# secon_analog_in.net
KiCad netlist of a schematic drawn in Altium Designer
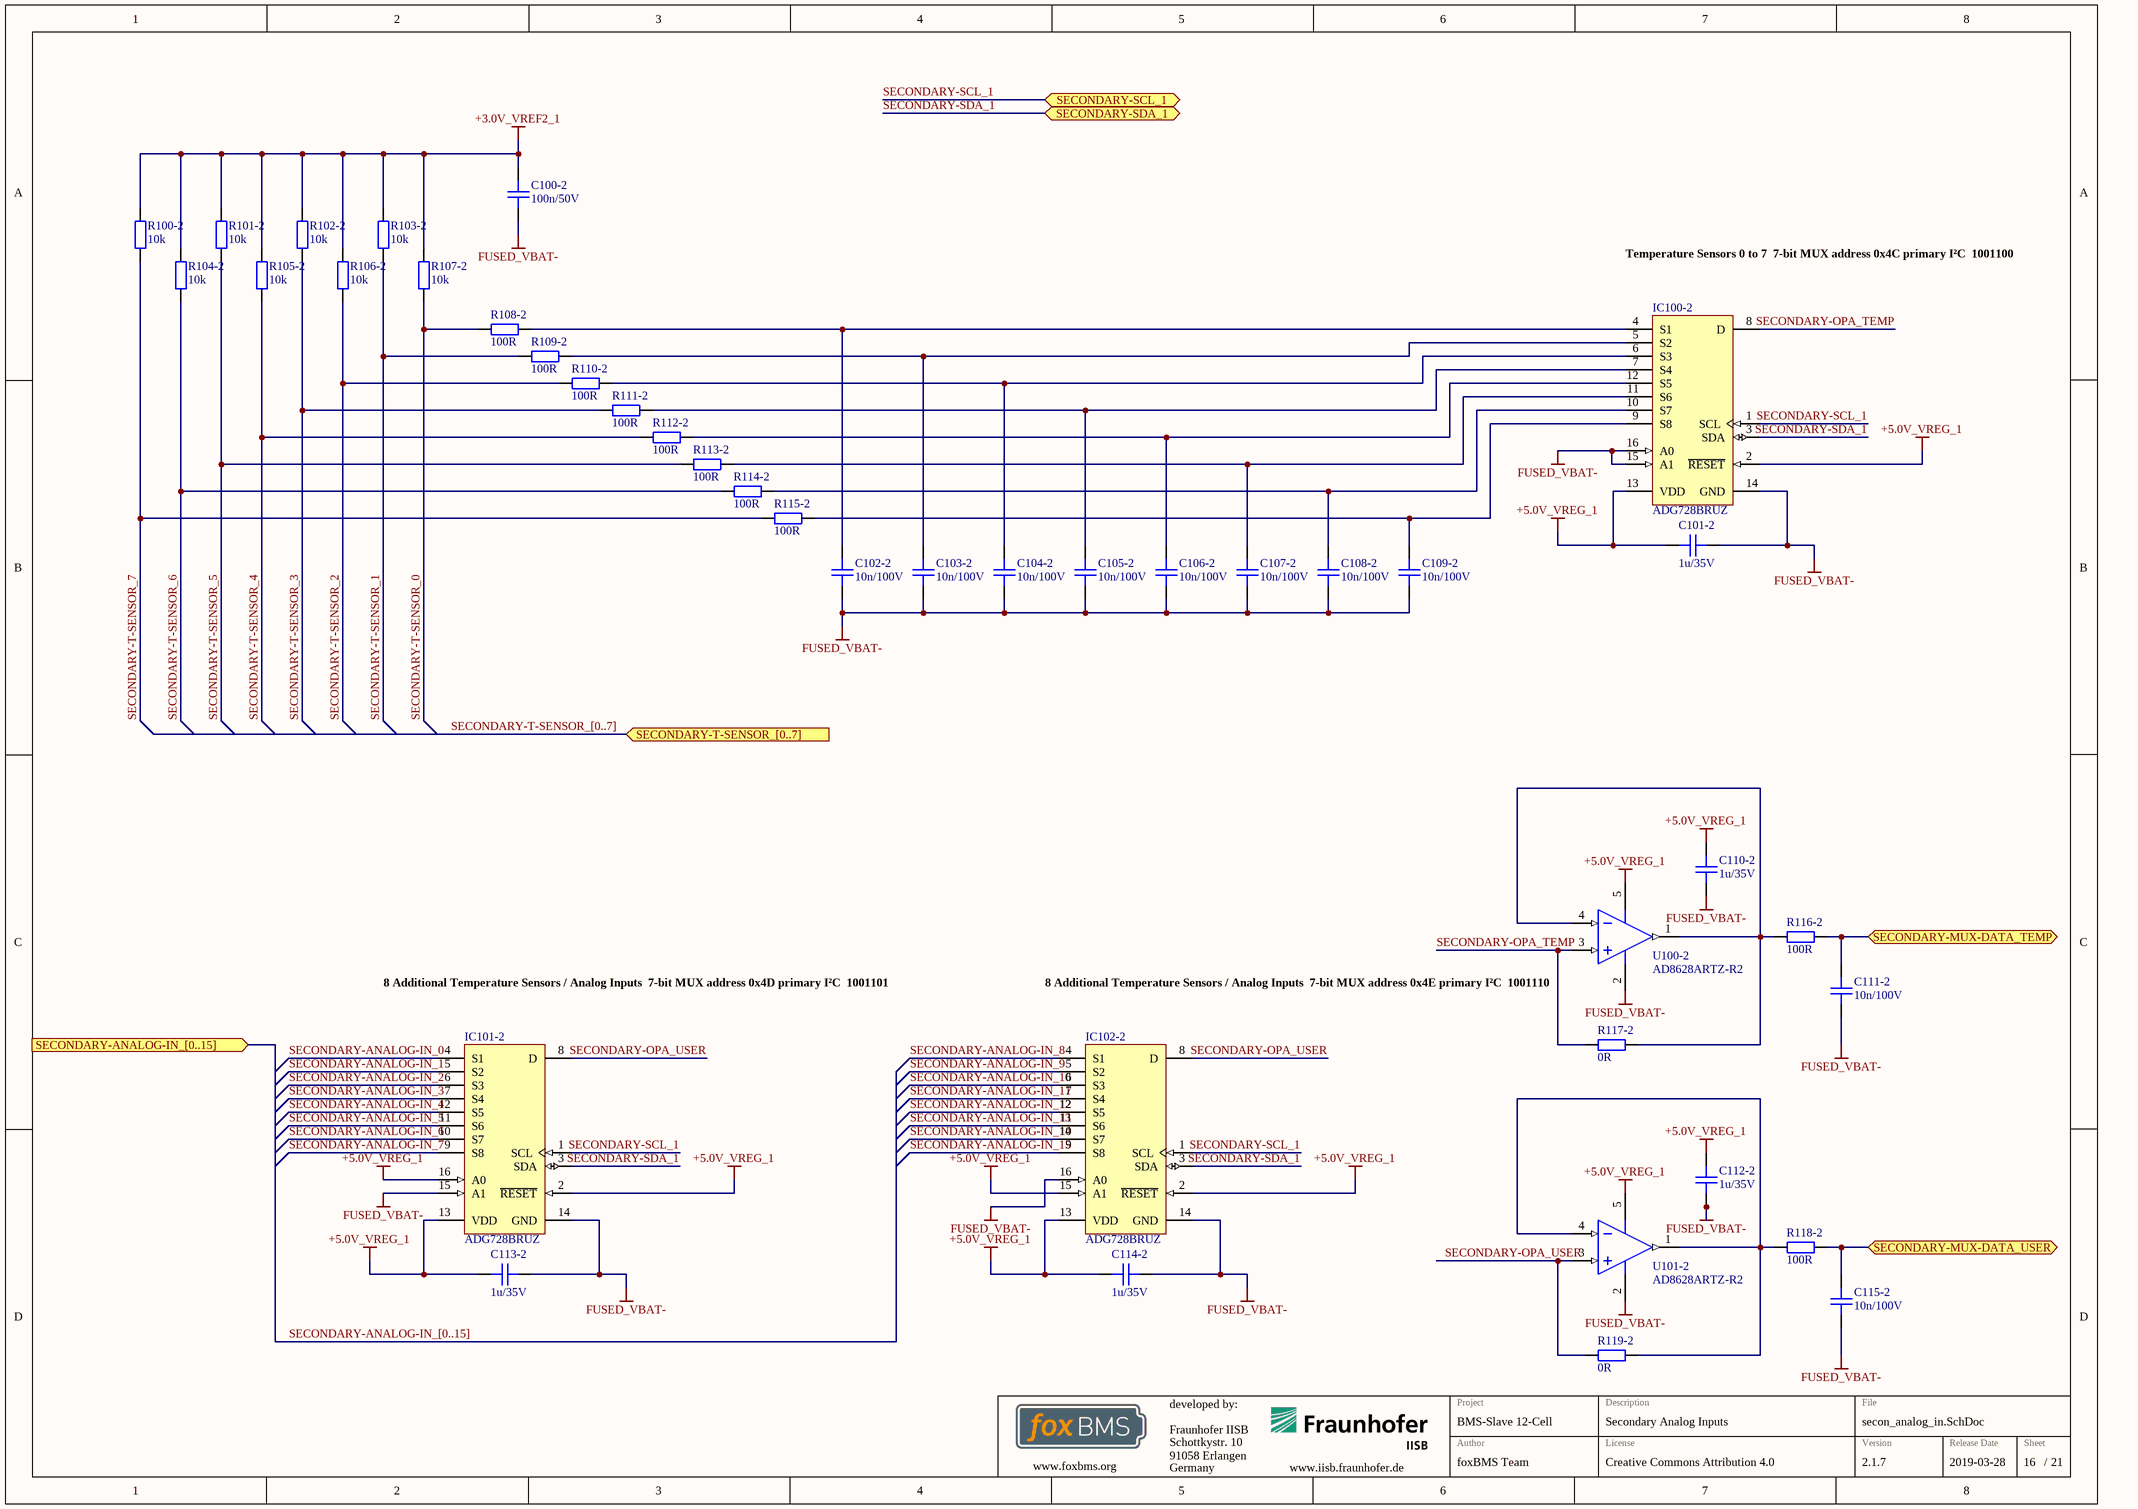
[diagram p0: secon_analog_in.SchDoc]

(export (version "E")
  (design (tool "Eeschema 10.0.6"))
  (components
    (comp (ref "C100-2")
      (value "100n/50V")
      (footprint "CAPC1608X08N")
      (description "MLCC")
      (fields (field (name "PART NUMBER") "gen_C_ceramic_100n_50V_X7R_0603"))
      (libsource (lib "OE750") (part "C"))
    )
    (comp (ref "C101-2")
      (value "1u/35V")
      (footprint "CAPC1608X08N")
      (description "MLCC")
      (fields (field (name "PART NUMBER") "gen_C_ceramic_1u_35V_X7R_0603"))
      (libsource (lib "OE750") (part "C"))
    )
    (comp (ref "C102-2")
      (value "10n/100V")
      (footprint "CAPC1608X08N")
      (description "MLCC")
      (fields (field (name "PART NUMBER") "gen_C_ceramic_10n_100V_X7R_0603"))
      (libsource (lib "OE750") (part "C"))
    )
    (comp (ref "C103-2")
      (value "10n/100V")
      (footprint "CAPC1608X08N")
      (description "MLCC")
      (fields (field (name "PART NUMBER") "gen_C_ceramic_10n_100V_X7R_0603"))
      (libsource (lib "OE750") (part "C"))
    )
    (comp (ref "C104-2")
      (value "10n/100V")
      (footprint "CAPC1608X08N")
      (description "MLCC")
      (fields (field (name "PART NUMBER") "gen_C_ceramic_10n_100V_X7R_0603"))
      (libsource (lib "OE750") (part "C"))
    )
    (comp (ref "C105-2")
      (value "10n/100V")
      (footprint "CAPC1608X08N")
      (description "MLCC")
      (fields (field (name "PART NUMBER") "gen_C_ceramic_10n_100V_X7R_0603"))
      (libsource (lib "OE750") (part "C"))
    )
    (comp (ref "C106-2")
      (value "10n/100V")
      (footprint "CAPC1608X08N")
      (description "MLCC")
      (fields (field (name "PART NUMBER") "gen_C_ceramic_10n_100V_X7R_0603"))
      (libsource (lib "OE750") (part "C"))
    )
    (comp (ref "C107-2")
      (value "10n/100V")
      (footprint "CAPC1608X08N")
      (description "MLCC")
      (fields (field (name "PART NUMBER") "gen_C_ceramic_10n_100V_X7R_0603"))
      (libsource (lib "OE750") (part "C"))
    )
    (comp (ref "C108-2")
      (value "10n/100V")
      (footprint "CAPC1608X08N")
      (description "MLCC")
      (fields (field (name "PART NUMBER") "gen_C_ceramic_10n_100V_X7R_0603"))
      (libsource (lib "OE750") (part "C"))
    )
    (comp (ref "C109-2")
      (value "10n/100V")
      (footprint "CAPC1608X08N")
      (description "MLCC")
      (fields (field (name "PART NUMBER") "gen_C_ceramic_10n_100V_X7R_0603"))
      (libsource (lib "OE750") (part "C"))
    )
    (comp (ref "C110-2")
      (value "1u/35V")
      (footprint "CAPC1608X08N")
      (description "MLCC")
      (fields (field (name "PART NUMBER") "gen_C_ceramic_1u_35V_X7R_0603"))
      (libsource (lib "OE750") (part "C"))
    )
    (comp (ref "C111-2")
      (value "10n/100V")
      (footprint "CAPC1608X08N")
      (description "MLCC")
      (fields (field (name "PART NUMBER") "gen_C_ceramic_10n_100V_X7R_0603"))
      (libsource (lib "OE750") (part "C"))
    )
    (comp (ref "C112-2")
      (value "1u/35V")
      (footprint "CAPC1608X08N")
      (description "MLCC")
      (fields (field (name "PART NUMBER") "gen_C_ceramic_1u_35V_X7R_0603"))
      (libsource (lib "OE750") (part "C"))
    )
    (comp (ref "C113-2")
      (value "1u/35V")
      (footprint "CAPC1608X08N")
      (description "MLCC")
      (fields (field (name "PART NUMBER") "gen_C_ceramic_1u_35V_X7R_0603"))
      (libsource (lib "OE750") (part "C"))
    )
    (comp (ref "C114-2")
      (value "1u/35V")
      (footprint "CAPC1608X08N")
      (description "MLCC")
      (fields (field (name "PART NUMBER") "gen_C_ceramic_1u_35V_X7R_0603"))
      (libsource (lib "OE750") (part "C"))
    )
    (comp (ref "C115-2")
      (value "10n/100V")
      (footprint "CAPC1608X08N")
      (description "MLCC")
      (fields (field (name "PART NUMBER") "gen_C_ceramic_10n_100V_X7R_0603"))
      (libsource (lib "OE750") (part "C"))
    )
    (comp (ref "IC100-2")
      (value "ADG728BRUZ")
      (footprint "ADI-RU-16_M")
      (fields (field (name "MANUFACTURER") "Analog Devices"))
      (libsource (lib "Altium Content Vault") (part "ADI-ADG728-RU-16"))
    )
    (comp (ref "IC101-2")
      (value "ADG728BRUZ")
      (footprint "ADI-RU-16_M")
      (fields (field (name "MANUFACTURER") "Analog Devices"))
      (libsource (lib "Altium Content Vault") (part "ADI-ADG728-RU-16"))
    )
    (comp (ref "IC102-2")
      (value "ADG728BRUZ")
      (footprint "ADI-RU-16_M")
      (fields (field (name "MANUFACTURER") "Analog Devices"))
      (libsource (lib "Altium Content Vault") (part "ADI-ADG728-RU-16"))
    )
    (comp (ref "R100-2")
      (value "10k")
      (footprint "RESC1608X05N")
      (description "SMD Resistor 10k 0603")
      (fields (field (name "PART NUMBER") "gen_R_10k_0603") (field (name "TOLERANCE") "1%"))
      (libsource (lib "OE750") (part "R"))
    )
    (comp (ref "R101-2")
      (value "10k")
      (footprint "RESC1608X05N")
      (description "SMD Resistor 10k 0603")
      (fields (field (name "PART NUMBER") "gen_R_10k_0603") (field (name "TOLERANCE") "1%"))
      (libsource (lib "OE750") (part "R"))
    )
    (comp (ref "R102-2")
      (value "10k")
      (footprint "RESC1608X05N")
      (description "SMD Resistor 10k 0603")
      (fields (field (name "PART NUMBER") "gen_R_10k_0603") (field (name "TOLERANCE") "1%"))
      (libsource (lib "OE750") (part "R"))
    )
    (comp (ref "R103-2")
      (value "10k")
      (footprint "RESC1608X05N")
      (description "SMD Resistor 10k 0603")
      (fields (field (name "PART NUMBER") "gen_R_10k_0603") (field (name "TOLERANCE") "1%"))
      (libsource (lib "OE750") (part "R"))
    )
    (comp (ref "R104-2")
      (value "10k")
      (footprint "RESC1608X05N")
      (description "SMD Resistor 10k 0603")
      (fields (field (name "PART NUMBER") "gen_R_10k_0603") (field (name "TOLERANCE") "1%"))
      (libsource (lib "OE750") (part "R"))
    )
    (comp (ref "R105-2")
      (value "10k")
      (footprint "RESC1608X05N")
      (description "SMD Resistor 10k 0603")
      (fields (field (name "PART NUMBER") "gen_R_10k_0603") (field (name "TOLERANCE") "1%"))
      (libsource (lib "OE750") (part "R"))
    )
    (comp (ref "R106-2")
      (value "10k")
      (footprint "RESC1608X05N")
      (description "SMD Resistor 10k 0603")
      (fields (field (name "PART NUMBER") "gen_R_10k_0603") (field (name "TOLERANCE") "1%"))
      (libsource (lib "OE750") (part "R"))
    )
    (comp (ref "R107-2")
      (value "10k")
      (footprint "RESC1608X05N")
      (description "SMD Resistor 10k 0603")
      (fields (field (name "PART NUMBER") "gen_R_10k_0603") (field (name "TOLERANCE") "1%"))
      (libsource (lib "OE750") (part "R"))
    )
    (comp (ref "R108-2")
      (value "100R")
      (footprint "RESC1608X05N")
      (description "SMD Resistor 100R 0603")
      (fields (field (name "PART NUMBER") "gen_R_100R_0603") (field (name "TOLERANCE") "1%"))
      (libsource (lib "OE750") (part "R"))
    )
    (comp (ref "R109-2")
      (value "100R")
      (footprint "RESC1608X05N")
      (description "SMD Resistor 100R 0603")
      (fields (field (name "PART NUMBER") "gen_R_100R_0603") (field (name "TOLERANCE") "1%"))
      (libsource (lib "OE750") (part "R"))
    )
    (comp (ref "R110-2")
      (value "100R")
      (footprint "RESC1608X05N")
      (description "SMD Resistor 100R 0603")
      (fields (field (name "PART NUMBER") "gen_R_100R_0603") (field (name "TOLERANCE") "1%"))
      (libsource (lib "OE750") (part "R"))
    )
    (comp (ref "R111-2")
      (value "100R")
      (footprint "RESC1608X05N")
      (description "SMD Resistor 100R 0603")
      (fields (field (name "PART NUMBER") "gen_R_100R_0603") (field (name "TOLERANCE") "1%"))
      (libsource (lib "OE750") (part "R"))
    )
    (comp (ref "R112-2")
      (value "100R")
      (footprint "RESC1608X05N")
      (description "SMD Resistor 100R 0603")
      (fields (field (name "PART NUMBER") "gen_R_100R_0603") (field (name "TOLERANCE") "1%"))
      (libsource (lib "OE750") (part "R"))
    )
    (comp (ref "R113-2")
      (value "100R")
      (footprint "RESC1608X05N")
      (description "SMD Resistor 100R 0603")
      (fields (field (name "PART NUMBER") "gen_R_100R_0603") (field (name "TOLERANCE") "1%"))
      (libsource (lib "OE750") (part "R"))
    )
    (comp (ref "R114-2")
      (value "100R")
      (footprint "RESC1608X05N")
      (description "SMD Resistor 100R 0603")
      (fields (field (name "PART NUMBER") "gen_R_100R_0603") (field (name "TOLERANCE") "1%"))
      (libsource (lib "OE750") (part "R"))
    )
    (comp (ref "R115-2")
      (value "100R")
      (footprint "RESC1608X05N")
      (description "SMD Resistor 100R 0603")
      (fields (field (name "PART NUMBER") "gen_R_100R_0603") (field (name "TOLERANCE") "1%"))
      (libsource (lib "OE750") (part "R"))
    )
    (comp (ref "R116-2")
      (value "100R")
      (footprint "RESC1608X05N")
      (description "SMD Resistor 100R 0603")
      (fields (field (name "PART NUMBER") "gen_R_100R_0603") (field (name "TOLERANCE") "1%"))
      (libsource (lib "OE750") (part "R"))
    )
    (comp (ref "R117-2")
      (value "0R")
      (footprint "RESC1608X05N")
      (description "SMD Resistor 0R 0603")
      (fields (field (name "PART NUMBER") "gen_R_0R_0603") (field (name "POWER") "0.1W"))
      (libsource (lib "OE750") (part "R"))
    )
    (comp (ref "R118-2")
      (value "100R")
      (footprint "RESC1608X05N")
      (description "SMD Resistor 100R 0603")
      (fields (field (name "PART NUMBER") "gen_R_100R_0603") (field (name "TOLERANCE") "1%"))
      (libsource (lib "OE750") (part "R"))
    )
    (comp (ref "R119-2")
      (value "0R")
      (footprint "RESC1608X05N")
      (description "SMD Resistor 0R 0603")
      (fields (field (name "PART NUMBER") "gen_R_0R_0603") (field (name "POWER") "0.1W"))
      (libsource (lib "OE750") (part "R"))
    )
    (comp (ref "U100-2")
      (value "AD8628ARTZ-R2")
      (footprint "ADI-RJ-5_M")
      (fields (field (name "MANUFACTURER") "Analog Devices") (field (name "GENERIC PART NUMBER") "AD8628"))
      (libsource (lib "Altium Content Vault") (part "ADI-ADxxxx-X-5"))
    )
    (comp (ref "U101-2")
      (value "AD8628ARTZ-R2")
      (footprint "ADI-RJ-5_M")
      (fields (field (name "MANUFACTURER") "Analog Devices") (field (name "GENERIC PART NUMBER") "AD8628"))
      (libsource (lib "Altium Content Vault") (part "ADI-ADxxxx-X-5"))
    )
  )
  (nets
    (net (code "1") (name "+3.0V_VREF2_1") (class "Default")
      (node (ref "C100-2") (pin "2") (pinfunction "2_2") (pintype "passive"))
      (node (ref "R100-2") (pin "2") (pinfunction "2_2") (pintype "passive"))
      (node (ref "R101-2") (pin "2") (pinfunction "2_2") (pintype "passive"))
      (node (ref "R102-2") (pin "2") (pinfunction "2_2") (pintype "passive"))
      (node (ref "R103-2") (pin "2") (pinfunction "2_2") (pintype "passive"))
      (node (ref "R104-2") (pin "2") (pinfunction "2_2") (pintype "passive"))
      (node (ref "R105-2") (pin "2") (pinfunction "2_2") (pintype "passive"))
      (node (ref "R106-2") (pin "2") (pinfunction "2_2") (pintype "passive"))
      (node (ref "R107-2") (pin "2") (pinfunction "2_2") (pintype "passive"))
    )
    (net (code "2") (name "+5.0V_VREG_1") (class "Default")
      (node (ref "C101-2") (pin "2") (pinfunction "2_2") (pintype "passive"))
      (node (ref "C110-2") (pin "2") (pinfunction "2_2") (pintype "passive"))
      (node (ref "C112-2") (pin "2") (pinfunction "2_2") (pintype "passive"))
      (node (ref "C113-2") (pin "2") (pinfunction "2_2") (pintype "passive"))
      (node (ref "C114-2") (pin "2") (pinfunction "2_2") (pintype "passive"))
      (node (ref "IC100-2") (pin "13") (pinfunction "VDD_13") (pintype "power_in"))
      (node (ref "IC100-2") (pin "2") (pinfunction "~{RESET}_2") (pintype "input"))
      (node (ref "IC101-2") (pin "13") (pinfunction "VDD_13") (pintype "power_in"))
      (node (ref "IC101-2") (pin "16") (pinfunction "A0_16") (pintype "input"))
      (node (ref "IC101-2") (pin "2") (pinfunction "~{RESET}_2") (pintype "input"))
      (node (ref "IC102-2") (pin "13") (pinfunction "VDD_13") (pintype "power_in"))
      (node (ref "IC102-2") (pin "15") (pinfunction "A1_15") (pintype "input"))
      (node (ref "IC102-2") (pin "2") (pinfunction "~{RESET}_2") (pintype "input"))
      (node (ref "U100-2") (pin "5") (pinfunction "+V_5") (pintype "power_in"))
      (node (ref "U101-2") (pin "5") (pinfunction "+V_5") (pintype "power_in"))
    )
    (net (code "3") (name "/SECONDARY-ANALOG-IN_0") (class "Default")
      (node (ref "IC101-2") (pin "4") (pinfunction "S1_4") (pintype "passive"))
    )
    (net (code "4") (name "/SECONDARY-ANALOG-IN_1") (class "Default")
      (node (ref "IC101-2") (pin "5") (pinfunction "S2_5") (pintype "passive"))
    )
    (net (code "5") (name "/SECONDARY-ANALOG-IN_2") (class "Default")
      (node (ref "IC101-2") (pin "6") (pinfunction "S3_6") (pintype "passive"))
    )
    (net (code "6") (name "/SECONDARY-ANALOG-IN_3") (class "Default")
      (node (ref "IC101-2") (pin "7") (pinfunction "S4_7") (pintype "passive"))
    )
    (net (code "7") (name "/SECONDARY-ANALOG-IN_4") (class "Default")
      (node (ref "IC101-2") (pin "12") (pinfunction "S5_12") (pintype "passive"))
    )
    (net (code "8") (name "/SECONDARY-ANALOG-IN_5") (class "Default")
      (node (ref "IC101-2") (pin "11") (pinfunction "S6_11") (pintype "passive"))
    )
    (net (code "9") (name "/SECONDARY-ANALOG-IN_6") (class "Default")
      (node (ref "IC101-2") (pin "10") (pinfunction "S7_10") (pintype "passive"))
    )
    (net (code "10") (name "/SECONDARY-ANALOG-IN_7") (class "Default")
      (node (ref "IC101-2") (pin "9") (pinfunction "S8_9") (pintype "passive"))
    )
    (net (code "11") (name "/SECONDARY-ANALOG-IN_8") (class "Default")
      (node (ref "IC102-2") (pin "4") (pinfunction "S1_4") (pintype "passive"))
    )
    (net (code "12") (name "/SECONDARY-ANALOG-IN_9") (class "Default")
      (node (ref "IC102-2") (pin "5") (pinfunction "S2_5") (pintype "passive"))
    )
    (net (code "13") (name "/SECONDARY-ANALOG-IN_10") (class "Default")
      (node (ref "IC102-2") (pin "6") (pinfunction "S3_6") (pintype "passive"))
    )
    (net (code "14") (name "/SECONDARY-ANALOG-IN_11") (class "Default")
      (node (ref "IC102-2") (pin "7") (pinfunction "S4_7") (pintype "passive"))
    )
    (net (code "15") (name "/SECONDARY-ANALOG-IN_12") (class "Default")
      (node (ref "IC102-2") (pin "12") (pinfunction "S5_12") (pintype "passive"))
    )
    (net (code "16") (name "/SECONDARY-ANALOG-IN_13") (class "Default")
      (node (ref "IC102-2") (pin "11") (pinfunction "S6_11") (pintype "passive"))
    )
    (net (code "17") (name "/SECONDARY-ANALOG-IN_14") (class "Default")
      (node (ref "IC102-2") (pin "10") (pinfunction "S7_10") (pintype "passive"))
    )
    (net (code "18") (name "/SECONDARY-ANALOG-IN_15") (class "Default")
      (node (ref "IC102-2") (pin "9") (pinfunction "S8_9") (pintype "passive"))
    )
    (net (code "20") (name "/SECONDARY-MUX-DATA_TEMP") (class "Default")
      (node (ref "C111-2") (pin "2") (pinfunction "2_2") (pintype "passive"))
      (node (ref "R116-2") (pin "2") (pinfunction "2_2") (pintype "passive"))
    )
    (net (code "21") (name "/SECONDARY-MUX-DATA_USER") (class "Default")
      (node (ref "C115-2") (pin "2") (pinfunction "2_2") (pintype "passive"))
      (node (ref "R118-2") (pin "2") (pinfunction "2_2") (pintype "passive"))
    )
    (net (code "22") (name "/SECONDARY-OPA_TEMP") (class "Default")
      (node (ref "IC100-2") (pin "8") (pinfunction "D_8") (pintype "passive"))
      (node (ref "R117-2") (pin "1") (pinfunction "1_1") (pintype "passive"))
      (node (ref "U100-2") (pin "3") (pinfunction "+IN_3") (pintype "input"))
    )
    (net (code "23") (name "/SECONDARY-OPA_USER") (class "Default")
      (node (ref "IC101-2") (pin "8") (pinfunction "D_8") (pintype "passive"))
      (node (ref "IC102-2") (pin "8") (pinfunction "D_8") (pintype "passive"))
      (node (ref "R119-2") (pin "1") (pinfunction "1_1") (pintype "passive"))
      (node (ref "U101-2") (pin "3") (pinfunction "+IN_3") (pintype "input"))
    )
    (net (code "24") (name "/SECONDARY-SCL_1") (class "Default")
      (node (ref "IC100-2") (pin "1") (pinfunction "SCL_1") (pintype "input"))
      (node (ref "IC101-2") (pin "1") (pinfunction "SCL_1") (pintype "input"))
      (node (ref "IC102-2") (pin "1") (pinfunction "SCL_1") (pintype "input"))
    )
    (net (code "25") (name "/SECONDARY-SDA_1") (class "Default")
      (node (ref "IC100-2") (pin "3") (pinfunction "SDA_3") (pintype "bidirectional"))
      (node (ref "IC101-2") (pin "3") (pinfunction "SDA_3") (pintype "bidirectional"))
      (node (ref "IC102-2") (pin "3") (pinfunction "SDA_3") (pintype "bidirectional"))
    )
    (net (code "26") (name "/SECONDARY-T-SENSOR_0") (class "Default")
      (node (ref "R107-2") (pin "1") (pinfunction "1_1") (pintype "passive"))
      (node (ref "R108-2") (pin "2") (pinfunction "2_2") (pintype "passive"))
    )
    (net (code "27") (name "/SECONDARY-T-SENSOR_1") (class "Default")
      (node (ref "R103-2") (pin "1") (pinfunction "1_1") (pintype "passive"))
      (node (ref "R109-2") (pin "2") (pinfunction "2_2") (pintype "passive"))
    )
    (net (code "28") (name "/SECONDARY-T-SENSOR_2") (class "Default")
      (node (ref "R106-2") (pin "1") (pinfunction "1_1") (pintype "passive"))
      (node (ref "R110-2") (pin "2") (pinfunction "2_2") (pintype "passive"))
    )
    (net (code "29") (name "/SECONDARY-T-SENSOR_3") (class "Default")
      (node (ref "R102-2") (pin "1") (pinfunction "1_1") (pintype "passive"))
      (node (ref "R111-2") (pin "2") (pinfunction "2_2") (pintype "passive"))
    )
    (net (code "30") (name "/SECONDARY-T-SENSOR_4") (class "Default")
      (node (ref "R105-2") (pin "1") (pinfunction "1_1") (pintype "passive"))
      (node (ref "R112-2") (pin "2") (pinfunction "2_2") (pintype "passive"))
    )
    (net (code "31") (name "/SECONDARY-T-SENSOR_5") (class "Default")
      (node (ref "R101-2") (pin "1") (pinfunction "1_1") (pintype "passive"))
      (node (ref "R113-2") (pin "2") (pinfunction "2_2") (pintype "passive"))
    )
    (net (code "32") (name "/SECONDARY-T-SENSOR_6") (class "Default")
      (node (ref "R104-2") (pin "1") (pinfunction "1_1") (pintype "passive"))
      (node (ref "R114-2") (pin "2") (pinfunction "2_2") (pintype "passive"))
    )
    (net (code "33") (name "/SECONDARY-T-SENSOR_7") (class "Default")
      (node (ref "R100-2") (pin "1") (pinfunction "1_1") (pintype "passive"))
      (node (ref "R115-2") (pin "2") (pinfunction "2_2") (pintype "passive"))
    )
    (net (code "35") (name "FUSED_VBAT-") (class "Default")
      (node (ref "C100-2") (pin "1") (pinfunction "1_1") (pintype "passive"))
      (node (ref "C101-2") (pin "1") (pinfunction "1_1") (pintype "passive"))
      (node (ref "C102-2") (pin "1") (pinfunction "1_1") (pintype "passive"))
      (node (ref "C103-2") (pin "1") (pinfunction "1_1") (pintype "passive"))
      (node (ref "C104-2") (pin "1") (pinfunction "1_1") (pintype "passive"))
      (node (ref "C105-2") (pin "1") (pinfunction "1_1") (pintype "passive"))
      (node (ref "C106-2") (pin "1") (pinfunction "1_1") (pintype "passive"))
      (node (ref "C107-2") (pin "1") (pinfunction "1_1") (pintype "passive"))
      (node (ref "C108-2") (pin "1") (pinfunction "1_1") (pintype "passive"))
      (node (ref "C109-2") (pin "1") (pinfunction "1_1") (pintype "passive"))
      (node (ref "C110-2") (pin "1") (pinfunction "1_1") (pintype "passive"))
      (node (ref "C111-2") (pin "1") (pinfunction "1_1") (pintype "passive"))
      (node (ref "C112-2") (pin "1") (pinfunction "1_1") (pintype "passive"))
      (node (ref "C113-2") (pin "1") (pinfunction "1_1") (pintype "passive"))
      (node (ref "C114-2") (pin "1") (pinfunction "1_1") (pintype "passive"))
      (node (ref "C115-2") (pin "1") (pinfunction "1_1") (pintype "passive"))
      (node (ref "IC100-2") (pin "14") (pinfunction "GND_14") (pintype "power_in"))
      (node (ref "IC100-2") (pin "15") (pinfunction "A1_15") (pintype "input"))
      (node (ref "IC100-2") (pin "16") (pinfunction "A0_16") (pintype "input"))
      (node (ref "IC101-2") (pin "14") (pinfunction "GND_14") (pintype "power_in"))
      (node (ref "IC101-2") (pin "15") (pinfunction "A1_15") (pintype "input"))
      (node (ref "IC102-2") (pin "14") (pinfunction "GND_14") (pintype "power_in"))
      (node (ref "IC102-2") (pin "16") (pinfunction "A0_16") (pintype "input"))
      (node (ref "U100-2") (pin "2") (pinfunction "-V_2") (pintype "power_in"))
      (node (ref "U101-2") (pin "2") (pinfunction "-V_2") (pintype "power_in"))
    )
    (net (code "36") (name "Net-(IC100-2-S1)") (class "Default")
      (node (ref "C102-2") (pin "2") (pinfunction "2_2") (pintype "passive"))
      (node (ref "IC100-2") (pin "4") (pinfunction "S1_4") (pintype "passive"))
      (node (ref "R108-2") (pin "1") (pinfunction "1_1") (pintype "passive"))
    )
    (net (code "37") (name "Net-(IC100-2-S2)") (class "Default")
      (node (ref "C103-2") (pin "2") (pinfunction "2_2") (pintype "passive"))
      (node (ref "IC100-2") (pin "5") (pinfunction "S2_5") (pintype "passive"))
      (node (ref "R109-2") (pin "1") (pinfunction "1_1") (pintype "passive"))
    )
    (net (code "38") (name "Net-(IC100-2-S3)") (class "Default")
      (node (ref "C104-2") (pin "2") (pinfunction "2_2") (pintype "passive"))
      (node (ref "IC100-2") (pin "6") (pinfunction "S3_6") (pintype "passive"))
      (node (ref "R110-2") (pin "1") (pinfunction "1_1") (pintype "passive"))
    )
    (net (code "39") (name "Net-(IC100-2-S4)") (class "Default")
      (node (ref "C105-2") (pin "2") (pinfunction "2_2") (pintype "passive"))
      (node (ref "IC100-2") (pin "7") (pinfunction "S4_7") (pintype "passive"))
      (node (ref "R111-2") (pin "1") (pinfunction "1_1") (pintype "passive"))
    )
    (net (code "40") (name "Net-(IC100-2-S5)") (class "Default")
      (node (ref "C106-2") (pin "2") (pinfunction "2_2") (pintype "passive"))
      (node (ref "IC100-2") (pin "12") (pinfunction "S5_12") (pintype "passive"))
      (node (ref "R112-2") (pin "1") (pinfunction "1_1") (pintype "passive"))
    )
    (net (code "41") (name "Net-(IC100-2-S6)") (class "Default")
      (node (ref "C107-2") (pin "2") (pinfunction "2_2") (pintype "passive"))
      (node (ref "IC100-2") (pin "11") (pinfunction "S6_11") (pintype "passive"))
      (node (ref "R113-2") (pin "1") (pinfunction "1_1") (pintype "passive"))
    )
    (net (code "42") (name "Net-(IC100-2-S7)") (class "Default")
      (node (ref "C108-2") (pin "2") (pinfunction "2_2") (pintype "passive"))
      (node (ref "IC100-2") (pin "10") (pinfunction "S7_10") (pintype "passive"))
      (node (ref "R114-2") (pin "1") (pinfunction "1_1") (pintype "passive"))
    )
    (net (code "43") (name "Net-(IC100-2-S8)") (class "Default")
      (node (ref "C109-2") (pin "2") (pinfunction "2_2") (pintype "passive"))
      (node (ref "IC100-2") (pin "9") (pinfunction "S8_9") (pintype "passive"))
      (node (ref "R115-2") (pin "1") (pinfunction "1_1") (pintype "passive"))
    )
    (net (code "44") (name "Net-(U100-2--IN)") (class "Default")
      (node (ref "R116-2") (pin "1") (pinfunction "1_1") (pintype "passive"))
      (node (ref "R117-2") (pin "2") (pinfunction "2_2") (pintype "passive"))
      (node (ref "U100-2") (pin "1") (pinfunction "OUT_1") (pintype "output"))
      (node (ref "U100-2") (pin "4") (pinfunction "-IN_4") (pintype "input"))
    )
    (net (code "45") (name "Net-(U101-2--IN)") (class "Default")
      (node (ref "R118-2") (pin "1") (pinfunction "1_1") (pintype "passive"))
      (node (ref "R119-2") (pin "2") (pinfunction "2_2") (pintype "passive"))
      (node (ref "U101-2") (pin "1") (pinfunction "OUT_1") (pintype "output"))
      (node (ref "U101-2") (pin "4") (pinfunction "-IN_4") (pintype "input"))
    )
  )
)
